# STl-Link-V300.net
KiCad netlist of a schematic drawn in EAGLE
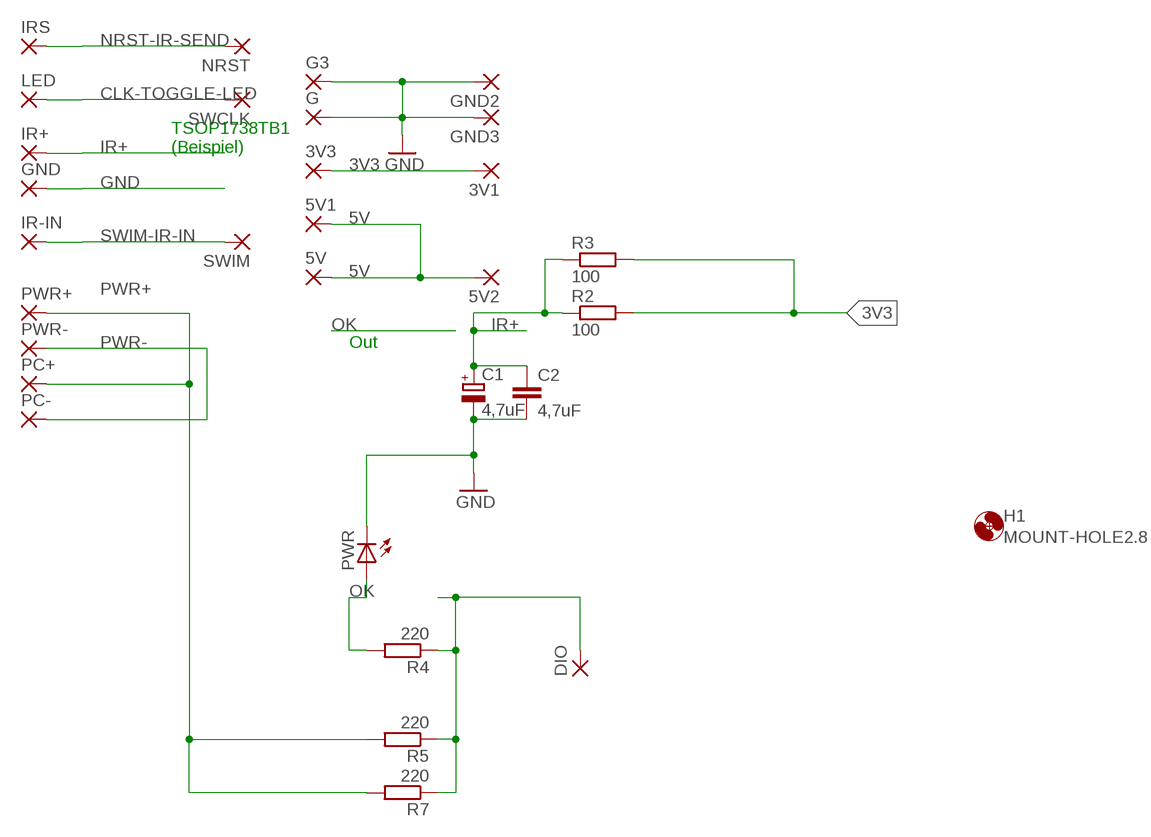
[diagram p0: schematic, sheet 1]

(export (version "E")
  (design (tool "Eeschema 10.0.6"))
  (components
    (comp (ref "3V1")
      (value "SMD2")
      (footprint "eagle-import:SMD1,27-2,54")
      (libsource (lib "eagle-import") (part "SMD2"))
    )
    (comp (ref "3V3")
      (value "SMD2")
      (footprint "eagle-import:SMD1,27-2,54")
      (libsource (lib "eagle-import") (part "SMD2"))
    )
    (comp (ref "5V")
      (value "SMD2")
      (footprint "eagle-import:SMD1,27-2,54")
      (libsource (lib "eagle-import") (part "SMD2"))
    )
    (comp (ref "5V1")
      (value "SMD2")
      (footprint "eagle-import:SMD1,27-2,54")
      (libsource (lib "eagle-import") (part "SMD2"))
    )
    (comp (ref "5V2")
      (value "SMD2")
      (footprint "eagle-import:SMD1,27-2,54")
      (libsource (lib "eagle-import") (part "SMD2"))
    )
    (comp (ref "C1")
      (value "4,7uF")
      (footprint "eagle-import:E1,8-4")
      (libsource (lib "eagle-import") (part "CPOL-EUE1.8-4"))
    )
    (comp (ref "C2")
      (value "4,7uF")
      (footprint "eagle-import:C1206K")
      (libsource (lib "eagle-import") (part "C-EUC1206K"))
    )
    (comp (ref "DIO")
      (value "SMD2")
      (footprint "eagle-import:SMD1,27-2,54")
      (libsource (lib "eagle-import") (part "SMD2"))
    )
    (comp (ref "G")
      (value "SMD2")
      (footprint "eagle-import:SMD1,27-2,54")
      (libsource (lib "eagle-import") (part "SMD2"))
    )
    (comp (ref "G3")
      (value "SMD2")
      (footprint "eagle-import:SMD1,27-2,54")
      (libsource (lib "eagle-import") (part "SMD2"))
    )
    (comp (ref "GND")
      (value "SMD2")
      (footprint "eagle-import:SMD1,27-2,54")
      (libsource (lib "eagle-import") (part "SMD2"))
    )
    (comp (ref "GND2")
      (value "SMD2")
      (footprint "eagle-import:SMD1,27-2,54")
      (libsource (lib "eagle-import") (part "SMD2"))
    )
    (comp (ref "GND3")
      (value "SMD2")
      (footprint "eagle-import:SMD1,27-2,54")
      (libsource (lib "eagle-import") (part "SMD2"))
    )
    (comp (ref "H1")
      (value "MOUNT-HOLE2.8")
      (footprint "eagle-import:2,8")
      (libsource (lib "eagle-import") (part "MOUNT-HOLE2.8"))
    )
    (comp (ref "IR+")
      (value "SMD2")
      (footprint "eagle-import:SMD1,27-2,54")
      (libsource (lib "eagle-import") (part "SMD2"))
    )
    (comp (ref "IR-IN")
      (value "SMD2")
      (footprint "eagle-import:SMD1,27-2,54")
      (libsource (lib "eagle-import") (part "SMD2"))
    )
    (comp (ref "IRS")
      (value "SMD2")
      (footprint "eagle-import:SMD1,27-2,54")
      (libsource (lib "eagle-import") (part "SMD2"))
    )
    (comp (ref "LED")
      (value "SMD2")
      (footprint "eagle-import:SMD1,27-2,54")
      (libsource (lib "eagle-import") (part "SMD2"))
    )
    (comp (ref "NRST")
      (value "SMD2")
      (footprint "eagle-import:SMD1,27-2,54")
      (libsource (lib "eagle-import") (part "SMD2"))
    )
    (comp (ref "PC+")
      (value "SMD2")
      (footprint "eagle-import:SMD1,27-2,54")
      (libsource (lib "eagle-import") (part "SMD2"))
    )
    (comp (ref "PC-")
      (value "SMD2")
      (footprint "eagle-import:SMD1,27-2,54")
      (libsource (lib "eagle-import") (part "SMD2"))
    )
    (comp (ref "PWR")
      (value "LEDCHIPLED_1206")
      (footprint "eagle-import:CHIPLED_1206")
      (libsource (lib "eagle-import") (part "LEDCHIPLED_1206"))
    )
    (comp (ref "PWR+")
      (value "SMD2")
      (footprint "eagle-import:SMD1,27-2,54")
      (libsource (lib "eagle-import") (part "SMD2"))
    )
    (comp (ref "PWR-")
      (value "SMD2")
      (footprint "eagle-import:SMD1,27-2,54")
      (libsource (lib "eagle-import") (part "SMD2"))
    )
    (comp (ref "R2")
      (value "100")
      (footprint "eagle-import:0204_7")
      (libsource (lib "eagle-import") (part "R-EU_0204/7"))
    )
    (comp (ref "R3")
      (value "100")
      (footprint "eagle-import:R0805W")
      (libsource (lib "eagle-import") (part "R-EU_R0805W"))
    )
    (comp (ref "R4")
      (value "220")
      (footprint "eagle-import:R0805W")
      (libsource (lib "eagle-import") (part "R-EU_R0805W"))
    )
    (comp (ref "R5")
      (value "220")
      (footprint "eagle-import:0204_7")
      (libsource (lib "eagle-import") (part "R-EU_0204/7"))
    )
    (comp (ref "R7")
      (value "220")
      (footprint "eagle-import:R0805W")
      (libsource (lib "eagle-import") (part "R-EU_R0805W"))
    )
    (comp (ref "SWCLK")
      (value "SMD2")
      (footprint "eagle-import:SMD1,27-2,54")
      (libsource (lib "eagle-import") (part "SMD2"))
    )
    (comp (ref "SWIM")
      (value "SMD2")
      (footprint "eagle-import:SMD1,27-2,54")
      (libsource (lib "eagle-import") (part "SMD2"))
    )
  )
  (nets
    (net (code "1") (name "/5V") (class "Default")
      (node (ref "5V") (pin "1") (pinfunction "P_1") (pintype "passive"))
      (node (ref "5V1") (pin "1") (pinfunction "P_1") (pintype "passive"))
      (node (ref "5V2") (pin "1") (pinfunction "P_1") (pintype "passive"))
    )
    (net (code "2") (name "/CLK-TOGGLE-LED") (class "Default")
      (node (ref "LED") (pin "1") (pinfunction "P_1") (pintype "passive"))
      (node (ref "SWCLK") (pin "1") (pinfunction "P_1") (pintype "passive"))
    )
    (net (code "3") (name "/IR+") (class "Default")
      (node (ref "C1") (pin "+") (pinfunction "+_+") (pintype "passive"))
      (node (ref "C2") (pin "1") (pinfunction "1_1") (pintype "passive"))
      (node (ref "IR+") (pin "1") (pinfunction "P_1") (pintype "passive"))
      (node (ref "R2") (pin "1") (pinfunction "1_1") (pintype "passive"))
      (node (ref "R3") (pin "1") (pinfunction "1_1") (pintype "passive"))
    )
    (net (code "4") (name "/NRST-IR-SEND") (class "Default")
      (node (ref "IRS") (pin "1") (pinfunction "P_1") (pintype "passive"))
      (node (ref "NRST") (pin "1") (pinfunction "P_1") (pintype "passive"))
    )
    (net (code "5") (name "/OK") (class "Default")
      (node (ref "PWR") (pin "A") (pinfunction "A_A") (pintype "passive"))
      (node (ref "R4") (pin "2") (pinfunction "2_2") (pintype "passive"))
    )
    (net (code "6") (name "/PWR+") (class "Default")
      (node (ref "PC+") (pin "1") (pinfunction "P_1") (pintype "passive"))
      (node (ref "PWR+") (pin "1") (pinfunction "P_1") (pintype "passive"))
      (node (ref "R5") (pin "2") (pinfunction "2_2") (pintype "passive"))
      (node (ref "R7") (pin "2") (pinfunction "2_2") (pintype "passive"))
    )
    (net (code "7") (name "/PWR-") (class "Default")
      (node (ref "PC-") (pin "1") (pinfunction "P_1") (pintype "passive"))
      (node (ref "PWR-") (pin "1") (pinfunction "P_1") (pintype "passive"))
    )
    (net (code "8") (name "/SWIM-IR-IN") (class "Default")
      (node (ref "IR-IN") (pin "1") (pinfunction "P_1") (pintype "passive"))
      (node (ref "SWIM") (pin "1") (pinfunction "P_1") (pintype "passive"))
    )
    (net (code "9") (name "3V3") (class "Default")
      (node (ref "3V1") (pin "1") (pinfunction "P_1") (pintype "passive"))
      (node (ref "3V3") (pin "1") (pinfunction "P_1") (pintype "passive"))
      (node (ref "R2") (pin "2") (pinfunction "2_2") (pintype "passive"))
      (node (ref "R3") (pin "2") (pinfunction "2_2") (pintype "passive"))
    )
    (net (code "10") (name "GND") (class "Default")
      (node (ref "C1") (pin "-") (pinfunction "-_-") (pintype "passive"))
      (node (ref "C2") (pin "2") (pinfunction "2_2") (pintype "passive"))
      (node (ref "G") (pin "1") (pinfunction "P_1") (pintype "passive"))
      (node (ref "G3") (pin "1") (pinfunction "P_1") (pintype "passive"))
      (node (ref "GND") (pin "1") (pinfunction "P_1") (pintype "passive"))
      (node (ref "GND2") (pin "1") (pinfunction "P_1") (pintype "passive"))
      (node (ref "GND3") (pin "1") (pinfunction "P_1") (pintype "passive"))
      (node (ref "PWR") (pin "C") (pinfunction "C_C") (pintype "passive"))
    )
    (net (code "11") (name "Net-(DIO-P)") (class "Default")
      (node (ref "DIO") (pin "1") (pinfunction "P_1") (pintype "passive"))
      (node (ref "R4") (pin "1") (pinfunction "1_1") (pintype "passive"))
      (node (ref "R5") (pin "1") (pinfunction "1_1") (pintype "passive"))
      (node (ref "R7") (pin "1") (pinfunction "1_1") (pintype "passive"))
    )
  )
)
